# serial_relay.net
KiCad netlist of a schematic drawn in EAGLE
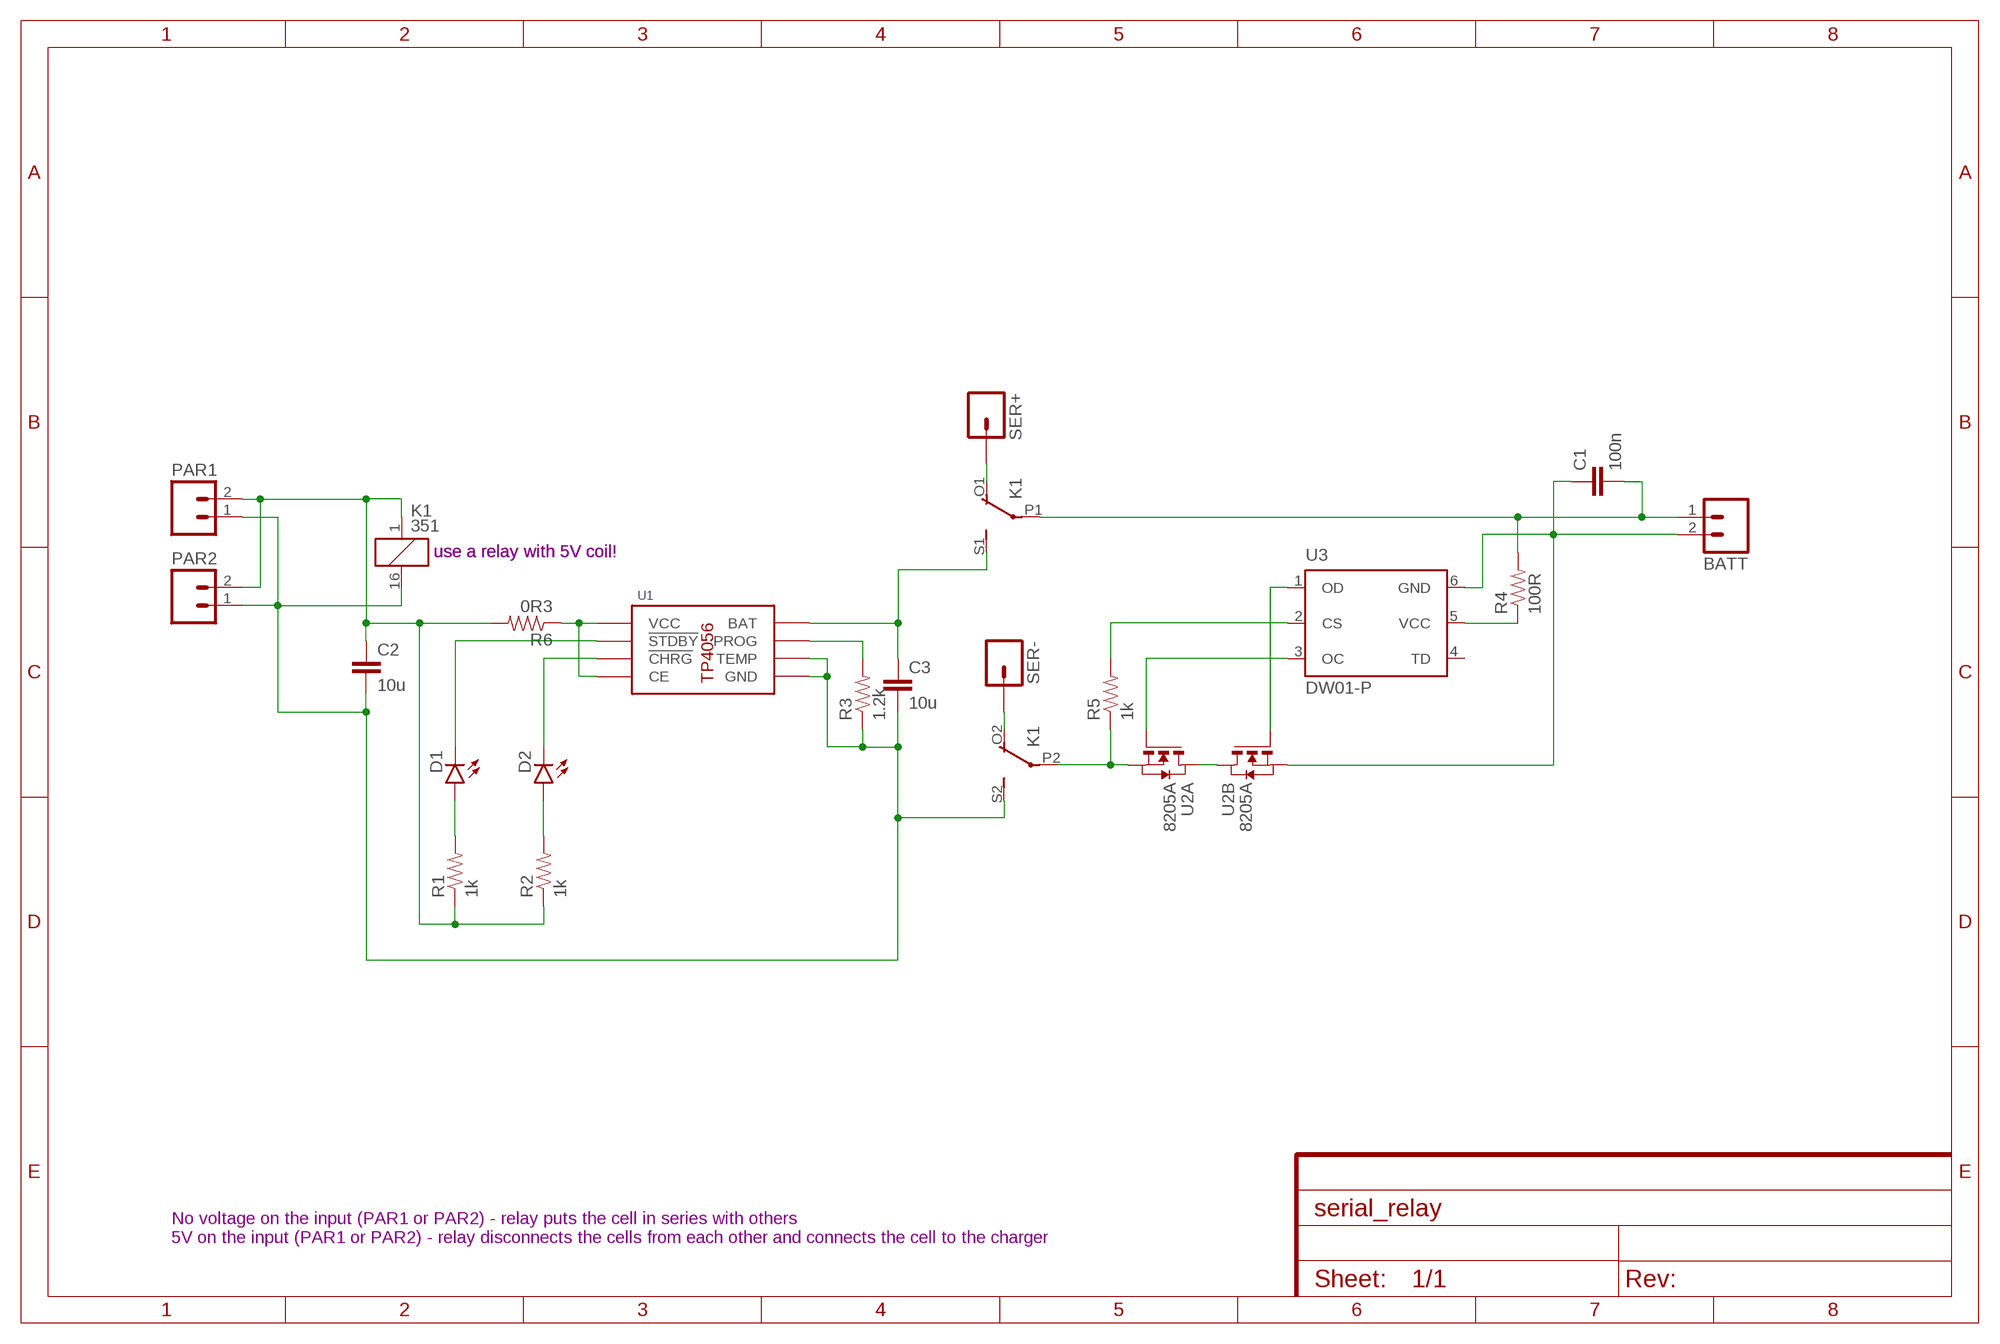
[diagram p0: schematic, sheet 1]

(export (version "E")
  (design (tool "Eeschema 10.0.6"))
  (components
    (comp (ref "BATT")
      (value "M02PTH3")
      (footprint "eagle-import:1X02_LONGPADS")
      (libsource (lib "eagle-import") (part "M02PTH3"))
    )
    (comp (ref "C1")
      (value "100n")
      (footprint "eagle-import:1206")
      (libsource (lib "eagle-import") (part "CAP1206"))
    )
    (comp (ref "C2")
      (value "10u")
      (footprint "eagle-import:1206")
      (libsource (lib "eagle-import") (part "CAP1206"))
    )
    (comp (ref "C3")
      (value "10u")
      (footprint "eagle-import:1206")
      (libsource (lib "eagle-import") (part "CAP1206"))
    )
    (comp (ref "D1")
      (value "LED1206")
      (footprint "eagle-import:LED-1206")
      (libsource (lib "eagle-import") (part "LED1206"))
    )
    (comp (ref "D2")
      (value "LED1206")
      (footprint "eagle-import:LED-1206")
      (libsource (lib "eagle-import") (part "LED1206"))
    )
    (comp (ref "K1")
      (value "351")
      (footprint "eagle-import:351")
      (libsource (lib "eagle-import") (part "351"))
    )
    (comp (ref "PAR1")
      (value "M02PTH3")
      (footprint "eagle-import:1X02_LONGPADS")
      (libsource (lib "eagle-import") (part "M02PTH3"))
    )
    (comp (ref "PAR2")
      (value "M02PTH3")
      (footprint "eagle-import:1X02_LONGPADS")
      (libsource (lib "eagle-import") (part "M02PTH3"))
    )
    (comp (ref "R1")
      (value "1k")
      (footprint "eagle-import:1206")
      (libsource (lib "eagle-import") (part "RESISTOR1206"))
    )
    (comp (ref "R2")
      (value "1k")
      (footprint "eagle-import:1206")
      (libsource (lib "eagle-import") (part "RESISTOR1206"))
    )
    (comp (ref "R3")
      (value "1.2k")
      (footprint "eagle-import:1206")
      (libsource (lib "eagle-import") (part "RESISTOR1206"))
    )
    (comp (ref "R4")
      (value "100R")
      (footprint "eagle-import:1206")
      (libsource (lib "eagle-import") (part "RESISTOR1206"))
    )
    (comp (ref "R5")
      (value "1k")
      (footprint "eagle-import:1206")
      (libsource (lib "eagle-import") (part "RESISTOR1206"))
    )
    (comp (ref "R6")
      (value "0R3")
      (footprint "eagle-import:1206")
      (libsource (lib "eagle-import") (part "RESISTOR1206"))
    )
    (comp (ref "SER+")
      (value "M01PTH_LONGPAD")
      (footprint "eagle-import:1X01_LONGPAD")
      (libsource (lib "eagle-import") (part "M01PTH_LONGPAD"))
    )
    (comp (ref "SER-")
      (value "M01PTH_LONGPAD")
      (footprint "eagle-import:1X01_LONGPAD")
      (libsource (lib "eagle-import") (part "M01PTH_LONGPAD"))
    )
    (comp (ref "U1")
      (value "TP4056")
      (footprint "eagle-import:SOP8")
      (libsource (lib "eagle-import") (part "TP4056"))
    )
    (comp (ref "U2")
      (value "8205A")
      (footprint "eagle-import:TSSOP8")
      (libsource (lib "eagle-import") (part "8205A"))
    )
    (comp (ref "U3")
      (value "DW01-P")
      (footprint "eagle-import:SOT23-6L")
      (libsource (lib "eagle-import") (part "DW01-P"))
    )
  )
  (nets
    (net (code "1") (name "Net-(C2-Pad1)") (class "Default")
      (node (ref "C2") (pin "1") (pinfunction "1_1") (pintype "passive"))
      (node (ref "K1") (pin "1") (pinfunction "1_1") (pintype "passive"))
      (node (ref "PAR1") (pin "2") (pinfunction "2_2") (pintype "passive"))
      (node (ref "PAR2") (pin "2") (pinfunction "2_2") (pintype "passive"))
      (node (ref "R1") (pin "1") (pinfunction "1_1") (pintype "passive"))
      (node (ref "R2") (pin "1") (pinfunction "1_1") (pintype "passive"))
      (node (ref "R6") (pin "2") (pinfunction "2_2") (pintype "passive"))
    )
    (net (code "2") (name "Net-(D1-PadA)") (class "Default")
      (node (ref "D1") (pin "A") (pinfunction "A_A") (pintype "passive"))
      (node (ref "R1") (pin "2") (pinfunction "2_2") (pintype "passive"))
    )
    (net (code "3") (name "Net-(D2-PadA)") (class "Default")
      (node (ref "D2") (pin "A") (pinfunction "A_A") (pintype "passive"))
      (node (ref "R2") (pin "2") (pinfunction "2_2") (pintype "passive"))
    )
    (net (code "4") (name "Net-(K1A-2)") (class "Default")
      (node (ref "C2") (pin "2") (pinfunction "2_2") (pintype "passive"))
      (node (ref "C3") (pin "2") (pinfunction "2_2") (pintype "passive"))
      (node (ref "K1") (pin "16") (pinfunction "2_16") (pintype "passive"))
      (node (ref "K1") (pin "S2") (pinfunction "S_S2") (pintype "passive"))
      (node (ref "PAR1") (pin "1") (pinfunction "1_1") (pintype "passive"))
      (node (ref "PAR2") (pin "1") (pinfunction "1_1") (pintype "passive"))
      (node (ref "R3") (pin "1") (pinfunction "1_1") (pintype "passive"))
      (node (ref "U1") (pin "1") (pinfunction "TEMP_1") (pintype "bidirectional"))
      (node (ref "U1") (pin "3") (pinfunction "GND_3") (pintype "bidirectional"))
    )
    (net (code "5") (name "Net-(K1B-O)") (class "Default")
      (node (ref "K1") (pin "O1") (pinfunction "O_O1") (pintype "passive"))
      (node (ref "SER+") (pin "1") (pinfunction "1_1") (pintype "passive"))
    )
    (net (code "6") (name "Net-(K1B-P)") (class "Default")
      (node (ref "BATT") (pin "1") (pinfunction "1_1") (pintype "passive"))
      (node (ref "C1") (pin "2") (pinfunction "2_2") (pintype "passive"))
      (node (ref "K1") (pin "P1") (pinfunction "P_P1") (pintype "passive"))
      (node (ref "R4") (pin "2") (pinfunction "2_2") (pintype "passive"))
    )
    (net (code "7") (name "Net-(K1B-S)") (class "Default")
      (node (ref "C3") (pin "1") (pinfunction "1_1") (pintype "passive"))
      (node (ref "K1") (pin "S1") (pinfunction "S_S1") (pintype "passive"))
      (node (ref "U1") (pin "5") (pinfunction "BAT_5") (pintype "bidirectional"))
    )
    (net (code "8") (name "Net-(K1C-O)") (class "Default")
      (node (ref "K1") (pin "O2") (pinfunction "O_O2") (pintype "passive"))
      (node (ref "SER-") (pin "1") (pinfunction "1_1") (pintype "passive"))
    )
    (net (code "9") (name "Net-(K1C-P)") (class "Default")
      (node (ref "K1") (pin "P2") (pinfunction "P_P2") (pintype "passive"))
      (node (ref "R5") (pin "1") (pinfunction "1_1") (pintype "passive"))
      (node (ref "U2") (pin "2") (pinfunction "S_2") (pintype "passive"))
      (node (ref "U2") (pin "3") (pinfunction "S_3") (pintype "passive"))
    )
    (net (code "10") (name "Net-(U1-CE)") (class "Default")
      (node (ref "R6") (pin "1") (pinfunction "1_1") (pintype "passive"))
      (node (ref "U1") (pin "4") (pinfunction "VCC_4") (pintype "bidirectional"))
      (node (ref "U1") (pin "8") (pinfunction "CE_8") (pintype "bidirectional"))
    )
    (net (code "11") (name "Net-(U1-PROG)") (class "Default")
      (node (ref "R3") (pin "2") (pinfunction "2_2") (pintype "passive"))
      (node (ref "U1") (pin "2") (pinfunction "PROG_2") (pintype "bidirectional"))
    )
    (net (code "12") (name "Net-(U1-~{CHRG})") (class "Default")
      (node (ref "D2") (pin "C") (pinfunction "C_C") (pintype "passive"))
      (node (ref "U1") (pin "7") (pinfunction "~{CHRG}_7") (pintype "bidirectional"))
    )
    (net (code "13") (name "Net-(U1-~{STDBY})") (class "Default")
      (node (ref "D1") (pin "C") (pinfunction "C_C") (pintype "passive"))
      (node (ref "U1") (pin "6") (pinfunction "~{STDBY}_6") (pintype "bidirectional"))
    )
    (net (code "14") (name "Net-(U2A-D)") (class "Default")
      (node (ref "U2") (pin "1") (pinfunction "D_1") (pintype "passive"))
      (node (ref "U2") (pin "8") (pinfunction "D_8") (pintype "passive"))
    )
    (net (code "15") (name "Net-(U2A-G)") (class "Default")
      (node (ref "U2") (pin "4") (pinfunction "G_4") (pintype "passive"))
      (node (ref "U3") (pin "3") (pinfunction "OC_3") (pintype "power_in"))
    )
    (net (code "16") (name "Net-(U2B-G)") (class "Default")
      (node (ref "U2") (pin "5") (pinfunction "G_5") (pintype "passive"))
      (node (ref "U3") (pin "1") (pinfunction "OD_1") (pintype "power_in"))
    )
    (net (code "17") (name "Net-(U3-CS)") (class "Default")
      (node (ref "R5") (pin "2") (pinfunction "2_2") (pintype "passive"))
      (node (ref "U3") (pin "2") (pinfunction "CS_2") (pintype "input"))
    )
    (net (code "18") (name "Net-(U3-GND)") (class "Default")
      (node (ref "BATT") (pin "2") (pinfunction "2_2") (pintype "passive"))
      (node (ref "C1") (pin "1") (pinfunction "1_1") (pintype "passive"))
      (node (ref "U2") (pin "6") (pinfunction "S_6") (pintype "passive"))
      (node (ref "U2") (pin "7") (pinfunction "S_7") (pintype "passive"))
      (node (ref "U3") (pin "6") (pinfunction "GND_6") (pintype "output"))
    )
    (net (code "19") (name "Net-(U3-VCC)") (class "Default")
      (node (ref "R4") (pin "1") (pinfunction "1_1") (pintype "passive"))
      (node (ref "U3") (pin "5") (pinfunction "VCC_5") (pintype "input"))
    )
    (net (code "20") (name "unconnected-(U3-TD-Pad4)") (class "Default")
      (node (ref "U3") (pin "4") (pinfunction "TD_4") (pintype "output"))
    )
  )
)
